# hpctrl.net
KiCad netlist of a schematic drawn in EAGLE
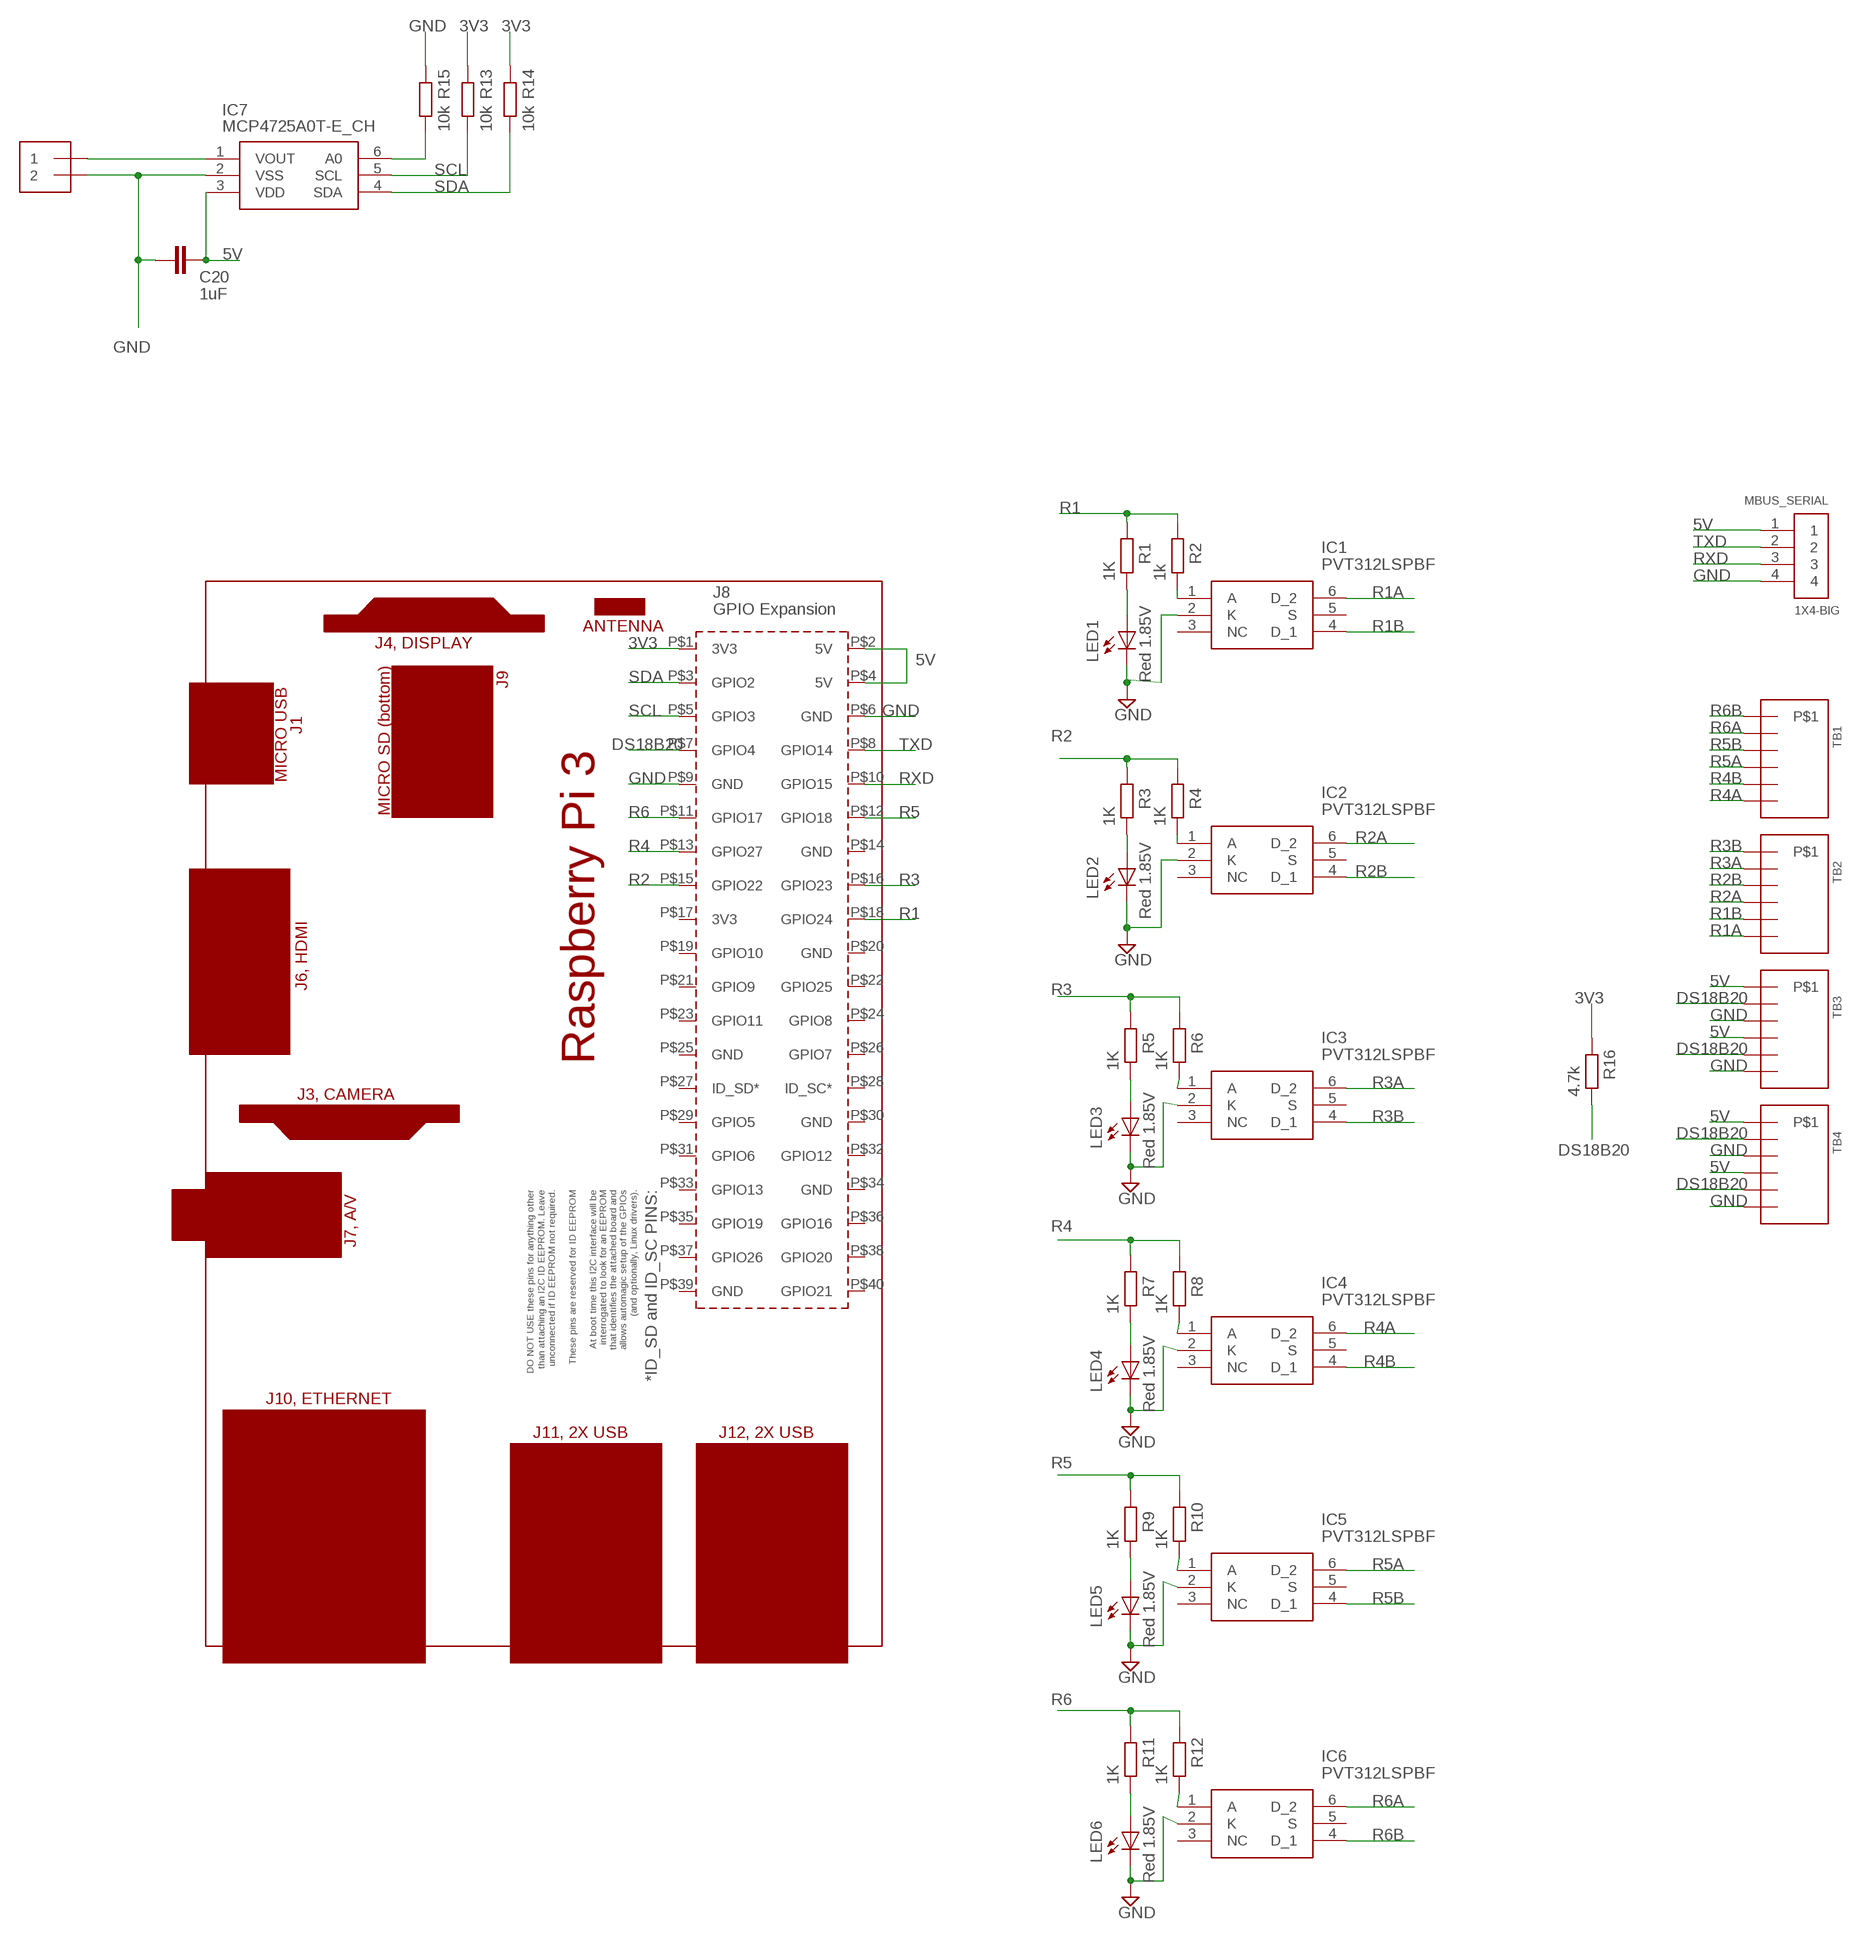
[diagram p0: schematic, sheet 1]

(export (version "E")
  (design (tool "Eeschema 10.0.6"))
  (components
    (comp (ref "C20")
      (value "1uF")
      (footprint "eagle-import:C0805")
      (libsource (lib "eagle-import") (part "C-EUC0805"))
    )
    (comp (ref "IC1")
      (value "PVT312LSPBF")
      (footprint "eagle-import:SOP254P978X342-6N")
      (fields (field (name "MOUSER_PART_NUMBER") "942-PVT312LSPBF"))
      (libsource (lib "eagle-import") (part "PVT312LSPBF"))
    )
    (comp (ref "IC2")
      (value "PVT312LSPBF")
      (footprint "eagle-import:SOP254P978X342-6N")
      (fields (field (name "MOUSER_PART_NUMBER") "942-PVT312LSPBF"))
      (libsource (lib "eagle-import") (part "PVT312LSPBF"))
    )
    (comp (ref "IC3")
      (value "PVT312LSPBF")
      (footprint "eagle-import:SOP254P978X342-6N")
      (fields (field (name "MOUSER_PART_NUMBER") "942-PVT312LSPBF"))
      (libsource (lib "eagle-import") (part "PVT312LSPBF"))
    )
    (comp (ref "IC4")
      (value "PVT312LSPBF")
      (footprint "eagle-import:SOP254P978X342-6N")
      (fields (field (name "MOUSER_PART_NUMBER") "942-PVT312LSPBF"))
      (libsource (lib "eagle-import") (part "PVT312LSPBF"))
    )
    (comp (ref "IC5")
      (value "PVT312LSPBF")
      (footprint "eagle-import:SOP254P978X342-6N")
      (fields (field (name "MOUSER_PART_NUMBER") "942-PVT312LSPBF"))
      (libsource (lib "eagle-import") (part "PVT312LSPBF"))
    )
    (comp (ref "IC6")
      (value "PVT312LSPBF")
      (footprint "eagle-import:SOP254P978X342-6N")
      (fields (field (name "MOUSER_PART_NUMBER") "942-PVT312LSPBF"))
      (libsource (lib "eagle-import") (part "PVT312LSPBF"))
    )
    (comp (ref "IC7")
      (value "MCP4725A0T-E_CH")
      (footprint "eagle-import:SOT95P270X145-6N")
      (fields
        (field (name "ARROW_PART_NUMBER") "MCP4725A0T-E/CH")
        (field (name "MOUSER_PART_NUMBER") "579-MCP4725A0TECH")
      )
      (libsource (lib "eagle-import") (part "MCP4725A0T-E_CH"))
    )
    (comp (ref "J1")
      (value "1X2-3.5MM")
      (footprint "eagle-import:1X2-3.5MM")
      (libsource (lib "eagle-import") (part "1X2-3.5MM"))
    )
    (comp (ref "LED1")
      (value "Red 1.85V")
      (footprint "eagle-import:CHIP-LED0805")
      (libsource (lib "eagle-import") (part "LEDCHIP-LED0805"))
    )
    (comp (ref "LED2")
      (value "Red 1.85V")
      (footprint "eagle-import:CHIP-LED0805")
      (libsource (lib "eagle-import") (part "LEDCHIP-LED0805"))
    )
    (comp (ref "LED3")
      (value "Red 1.85V")
      (footprint "eagle-import:CHIP-LED0805")
      (libsource (lib "eagle-import") (part "LEDCHIP-LED0805"))
    )
    (comp (ref "LED4")
      (value "Red 1.85V")
      (footprint "eagle-import:CHIP-LED0805")
      (libsource (lib "eagle-import") (part "LEDCHIP-LED0805"))
    )
    (comp (ref "LED5")
      (value "Red 1.85V")
      (footprint "eagle-import:CHIP-LED0805")
      (libsource (lib "eagle-import") (part "LEDCHIP-LED0805"))
    )
    (comp (ref "LED6")
      (value "Red 1.85V")
      (footprint "eagle-import:CHIP-LED0805")
      (libsource (lib "eagle-import") (part "LEDCHIP-LED0805"))
    )
    (comp (ref "MBUS_SERIAL")
      (value "1X4-BIG")
      (footprint "eagle-import:1X04-BIG")
      (libsource (lib "eagle-import") (part "1X4-BIG"))
    )
    (comp (ref "PCB1")
      (value "RPI3RPI3")
      (footprint "eagle-import:RPI3")
      (libsource (lib "eagle-import") (part "RPI3RPI3"))
    )
    (comp (ref "R1")
      (value "1K")
      (footprint "eagle-import:R0603")
      (libsource (lib "eagle-import") (part "R-EU_R0603"))
    )
    (comp (ref "R2")
      (value "1k")
      (footprint "eagle-import:R0603")
      (libsource (lib "eagle-import") (part "R-EU_R0603"))
    )
    (comp (ref "R3")
      (value "1K")
      (footprint "eagle-import:R0603")
      (libsource (lib "eagle-import") (part "R-EU_R0603"))
    )
    (comp (ref "R4")
      (value "1K")
      (footprint "eagle-import:R0603")
      (libsource (lib "eagle-import") (part "R-EU_R0603"))
    )
    (comp (ref "R5")
      (value "1K")
      (footprint "eagle-import:R0603")
      (libsource (lib "eagle-import") (part "R-EU_R0603"))
    )
    (comp (ref "R6")
      (value "1K")
      (footprint "eagle-import:R0603")
      (libsource (lib "eagle-import") (part "R-EU_R0603"))
    )
    (comp (ref "R7")
      (value "1K")
      (footprint "eagle-import:R0603")
      (libsource (lib "eagle-import") (part "R-EU_R0603"))
    )
    (comp (ref "R8")
      (value "1K")
      (footprint "eagle-import:R0603")
      (libsource (lib "eagle-import") (part "R-EU_R0603"))
    )
    (comp (ref "R9")
      (value "1K")
      (footprint "eagle-import:R0603")
      (libsource (lib "eagle-import") (part "R-EU_R0603"))
    )
    (comp (ref "R10")
      (value "1K")
      (footprint "eagle-import:R0603")
      (libsource (lib "eagle-import") (part "R-EU_R0603"))
    )
    (comp (ref "R11")
      (value "1K")
      (footprint "eagle-import:R0603")
      (libsource (lib "eagle-import") (part "R-EU_R0603"))
    )
    (comp (ref "R12")
      (value "1K")
      (footprint "eagle-import:R0603")
      (libsource (lib "eagle-import") (part "R-EU_R0603"))
    )
    (comp (ref "R13")
      (value "10k")
      (footprint "eagle-import:R0603")
      (libsource (lib "eagle-import") (part "R-EU_R0603"))
    )
    (comp (ref "R14")
      (value "10k")
      (footprint "eagle-import:R0603")
      (libsource (lib "eagle-import") (part "R-EU_R0603"))
    )
    (comp (ref "R15")
      (value "10k")
      (footprint "eagle-import:R0603")
      (libsource (lib "eagle-import") (part "R-EU_R0603"))
    )
    (comp (ref "R16")
      (value "4.7k")
      (footprint "eagle-import:R0603")
      (libsource (lib "eagle-import") (part "R-EU_R0603"))
    )
    (comp (ref "TB1")
      (value "3.5MM_TB_X6")
      (footprint "eagle-import:3.5MM_X6")
      (libsource (lib "eagle-import") (part "3.5MM_TB_X6"))
    )
    (comp (ref "TB2")
      (value "3.5MM_TB_X6")
      (footprint "eagle-import:3.5MM_X6")
      (libsource (lib "eagle-import") (part "3.5MM_TB_X6"))
    )
    (comp (ref "TB3")
      (value "3.5MM_TB_X6")
      (footprint "eagle-import:3.5MM_X6")
      (libsource (lib "eagle-import") (part "3.5MM_TB_X6"))
    )
    (comp (ref "TB4")
      (value "3.5MM_TB_X6")
      (footprint "eagle-import:3.5MM_X6")
      (libsource (lib "eagle-import") (part "3.5MM_TB_X6"))
    )
  )
  (nets
    (net (code "1") (name "/3V3") (class "Default")
      (node (ref "PCB1") (pin "P$1") (pinfunction "3V3_P$1") (pintype "bidirectional"))
      (node (ref "R13") (pin "2") (pinfunction "2_2") (pintype "passive"))
      (node (ref "R14") (pin "2") (pinfunction "2_2") (pintype "passive"))
      (node (ref "R16") (pin "2") (pinfunction "2_2") (pintype "passive"))
    )
    (net (code "2") (name "/5V") (class "Default")
      (node (ref "C20") (pin "1") (pinfunction "1_1") (pintype "passive"))
      (node (ref "IC7") (pin "3") (pinfunction "VDD_3") (pintype "bidirectional"))
      (node (ref "MBUS_SERIAL") (pin "1") (pinfunction "1_1") (pintype "bidirectional"))
      (node (ref "PCB1") (pin "P$2") (pinfunction "5V_P$2") (pintype "bidirectional"))
      (node (ref "PCB1") (pin "P$4") (pinfunction "5V_P$4") (pintype "bidirectional"))
      (node (ref "TB3") (pin "P$1") (pinfunction "P$1_P$1") (pintype "bidirectional"))
      (node (ref "TB3") (pin "P$4") (pinfunction "P$4_P$4") (pintype "bidirectional"))
      (node (ref "TB4") (pin "P$1") (pinfunction "P$1_P$1") (pintype "bidirectional"))
      (node (ref "TB4") (pin "P$4") (pinfunction "P$4_P$4") (pintype "bidirectional"))
    )
    (net (code "3") (name "/DS18B20") (class "Default")
      (node (ref "PCB1") (pin "P$7") (pinfunction "GPIO4_P$7") (pintype "bidirectional"))
      (node (ref "R16") (pin "1") (pinfunction "1_1") (pintype "passive"))
      (node (ref "TB3") (pin "P$2") (pinfunction "P$2_P$2") (pintype "bidirectional"))
      (node (ref "TB3") (pin "P$5") (pinfunction "P$5_P$5") (pintype "bidirectional"))
      (node (ref "TB4") (pin "P$2") (pinfunction "P$2_P$2") (pintype "bidirectional"))
      (node (ref "TB4") (pin "P$5") (pinfunction "P$5_P$5") (pintype "bidirectional"))
    )
    (net (code "4") (name "/R1") (class "Default")
      (node (ref "PCB1") (pin "P$18") (pinfunction "GPIO24_P$18") (pintype "bidirectional"))
      (node (ref "R1") (pin "2") (pinfunction "2_2") (pintype "passive"))
      (node (ref "R2") (pin "2") (pinfunction "2_2") (pintype "passive"))
    )
    (net (code "5") (name "/R1A") (class "Default")
      (node (ref "IC1") (pin "6") (pinfunction "D_2_6") (pintype "bidirectional"))
      (node (ref "TB2") (pin "P$6") (pinfunction "P$6_P$6") (pintype "bidirectional"))
    )
    (net (code "6") (name "/R1B") (class "Default")
      (node (ref "IC1") (pin "4") (pinfunction "D_1_4") (pintype "bidirectional"))
      (node (ref "TB2") (pin "P$5") (pinfunction "P$5_P$5") (pintype "bidirectional"))
    )
    (net (code "7") (name "/R2") (class "Default")
      (node (ref "PCB1") (pin "P$15") (pinfunction "GPIO22_P$15") (pintype "bidirectional"))
      (node (ref "R3") (pin "2") (pinfunction "2_2") (pintype "passive"))
      (node (ref "R4") (pin "2") (pinfunction "2_2") (pintype "passive"))
    )
    (net (code "8") (name "/R2A") (class "Default")
      (node (ref "IC2") (pin "6") (pinfunction "D_2_6") (pintype "bidirectional"))
      (node (ref "TB2") (pin "P$4") (pinfunction "P$4_P$4") (pintype "bidirectional"))
    )
    (net (code "9") (name "/R2B") (class "Default")
      (node (ref "IC2") (pin "4") (pinfunction "D_1_4") (pintype "bidirectional"))
      (node (ref "TB2") (pin "P$3") (pinfunction "P$3_P$3") (pintype "bidirectional"))
    )
    (net (code "10") (name "/R3") (class "Default")
      (node (ref "PCB1") (pin "P$16") (pinfunction "GPIO23_P$16") (pintype "bidirectional"))
      (node (ref "R5") (pin "2") (pinfunction "2_2") (pintype "passive"))
      (node (ref "R6") (pin "2") (pinfunction "2_2") (pintype "passive"))
    )
    (net (code "11") (name "/R3A") (class "Default")
      (node (ref "IC3") (pin "6") (pinfunction "D_2_6") (pintype "bidirectional"))
      (node (ref "TB2") (pin "P$2") (pinfunction "P$2_P$2") (pintype "bidirectional"))
    )
    (net (code "12") (name "/R3B") (class "Default")
      (node (ref "IC3") (pin "4") (pinfunction "D_1_4") (pintype "bidirectional"))
      (node (ref "TB2") (pin "P$1") (pinfunction "P$1_P$1") (pintype "bidirectional"))
    )
    (net (code "13") (name "/R4") (class "Default")
      (node (ref "PCB1") (pin "P$13") (pinfunction "GPIO27_P$13") (pintype "bidirectional"))
      (node (ref "R7") (pin "2") (pinfunction "2_2") (pintype "passive"))
      (node (ref "R8") (pin "2") (pinfunction "2_2") (pintype "passive"))
    )
    (net (code "14") (name "/R4A") (class "Default")
      (node (ref "IC4") (pin "6") (pinfunction "D_2_6") (pintype "bidirectional"))
      (node (ref "TB1") (pin "P$6") (pinfunction "P$6_P$6") (pintype "bidirectional"))
    )
    (net (code "15") (name "/R4B") (class "Default")
      (node (ref "IC4") (pin "4") (pinfunction "D_1_4") (pintype "bidirectional"))
      (node (ref "TB1") (pin "P$5") (pinfunction "P$5_P$5") (pintype "bidirectional"))
    )
    (net (code "16") (name "/R5") (class "Default")
      (node (ref "PCB1") (pin "P$12") (pinfunction "GPIO18_P$12") (pintype "bidirectional"))
      (node (ref "R10") (pin "2") (pinfunction "2_2") (pintype "passive"))
      (node (ref "R9") (pin "2") (pinfunction "2_2") (pintype "passive"))
    )
    (net (code "17") (name "/R5A") (class "Default")
      (node (ref "IC5") (pin "6") (pinfunction "D_2_6") (pintype "bidirectional"))
      (node (ref "TB1") (pin "P$4") (pinfunction "P$4_P$4") (pintype "bidirectional"))
    )
    (net (code "18") (name "/R5B") (class "Default")
      (node (ref "IC5") (pin "4") (pinfunction "D_1_4") (pintype "bidirectional"))
      (node (ref "TB1") (pin "P$3") (pinfunction "P$3_P$3") (pintype "bidirectional"))
    )
    (net (code "19") (name "/R6") (class "Default")
      (node (ref "PCB1") (pin "P$11") (pinfunction "GPIO17_P$11") (pintype "bidirectional"))
      (node (ref "R11") (pin "2") (pinfunction "2_2") (pintype "passive"))
      (node (ref "R12") (pin "2") (pinfunction "2_2") (pintype "passive"))
    )
    (net (code "20") (name "/R6A") (class "Default")
      (node (ref "IC6") (pin "6") (pinfunction "D_2_6") (pintype "bidirectional"))
      (node (ref "TB1") (pin "P$2") (pinfunction "P$2_P$2") (pintype "bidirectional"))
    )
    (net (code "21") (name "/R6B") (class "Default")
      (node (ref "IC6") (pin "4") (pinfunction "D_1_4") (pintype "bidirectional"))
      (node (ref "TB1") (pin "P$1") (pinfunction "P$1_P$1") (pintype "bidirectional"))
    )
    (net (code "22") (name "/RXD") (class "Default")
      (node (ref "MBUS_SERIAL") (pin "3") (pinfunction "3_3") (pintype "bidirectional"))
      (node (ref "PCB1") (pin "P$10") (pinfunction "GPIO15_P$10") (pintype "bidirectional"))
    )
    (net (code "23") (name "/SCL") (class "Default")
      (node (ref "IC7") (pin "5") (pinfunction "SCL_5") (pintype "bidirectional"))
      (node (ref "PCB1") (pin "P$5") (pinfunction "GPIO3_P$5") (pintype "bidirectional"))
      (node (ref "R13") (pin "1") (pinfunction "1_1") (pintype "passive"))
    )
    (net (code "24") (name "/SDA") (class "Default")
      (node (ref "IC7") (pin "4") (pinfunction "SDA_4") (pintype "bidirectional"))
      (node (ref "PCB1") (pin "P$3") (pinfunction "GPIO2_P$3") (pintype "bidirectional"))
      (node (ref "R14") (pin "1") (pinfunction "1_1") (pintype "passive"))
    )
    (net (code "25") (name "/TXD") (class "Default")
      (node (ref "MBUS_SERIAL") (pin "2") (pinfunction "2_2") (pintype "bidirectional"))
      (node (ref "PCB1") (pin "P$8") (pinfunction "GPIO14_P$8") (pintype "bidirectional"))
    )
    (net (code "26") (name "GND") (class "Default")
      (node (ref "C20") (pin "2") (pinfunction "2_2") (pintype "passive"))
      (node (ref "IC1") (pin "2") (pinfunction "K_2") (pintype "bidirectional"))
      (node (ref "IC2") (pin "2") (pinfunction "K_2") (pintype "bidirectional"))
      (node (ref "IC3") (pin "2") (pinfunction "K_2") (pintype "bidirectional"))
      (node (ref "IC4") (pin "2") (pinfunction "K_2") (pintype "bidirectional"))
      (node (ref "IC5") (pin "2") (pinfunction "K_2") (pintype "bidirectional"))
      (node (ref "IC6") (pin "2") (pinfunction "K_2") (pintype "bidirectional"))
      (node (ref "IC7") (pin "2") (pinfunction "VSS_2") (pintype "bidirectional"))
      (node (ref "J1") (pin "2") (pinfunction "2_2") (pintype "passive"))
      (node (ref "LED1") (pin "C") (pinfunction "C_C") (pintype "passive"))
      (node (ref "LED2") (pin "C") (pinfunction "C_C") (pintype "passive"))
      (node (ref "LED3") (pin "C") (pinfunction "C_C") (pintype "passive"))
      (node (ref "LED4") (pin "C") (pinfunction "C_C") (pintype "passive"))
      (node (ref "LED5") (pin "C") (pinfunction "C_C") (pintype "passive"))
      (node (ref "LED6") (pin "C") (pinfunction "C_C") (pintype "passive"))
      (node (ref "MBUS_SERIAL") (pin "4") (pinfunction "4_4") (pintype "bidirectional"))
      (node (ref "PCB1") (pin "P$6") (pinfunction "GND_P$6") (pintype "bidirectional"))
      (node (ref "PCB1") (pin "P$9") (pinfunction "GND_P$9") (pintype "bidirectional"))
      (node (ref "R15") (pin "2") (pinfunction "2_2") (pintype "passive"))
      (node (ref "TB3") (pin "P$3") (pinfunction "P$3_P$3") (pintype "bidirectional"))
      (node (ref "TB3") (pin "P$6") (pinfunction "P$6_P$6") (pintype "bidirectional"))
      (node (ref "TB4") (pin "P$3") (pinfunction "P$3_P$3") (pintype "bidirectional"))
      (node (ref "TB4") (pin "P$6") (pinfunction "P$6_P$6") (pintype "bidirectional"))
    )
    (net (code "27") (name "Net-(IC1-A)") (class "Default")
      (node (ref "IC1") (pin "1") (pinfunction "A_1") (pintype "bidirectional"))
      (node (ref "R2") (pin "1") (pinfunction "1_1") (pintype "passive"))
    )
    (net (code "28") (name "Net-(IC2-A)") (class "Default")
      (node (ref "IC2") (pin "1") (pinfunction "A_1") (pintype "bidirectional"))
      (node (ref "R4") (pin "1") (pinfunction "1_1") (pintype "passive"))
    )
    (net (code "29") (name "Net-(IC3-A)") (class "Default")
      (node (ref "IC3") (pin "1") (pinfunction "A_1") (pintype "bidirectional"))
      (node (ref "R6") (pin "1") (pinfunction "1_1") (pintype "passive"))
    )
    (net (code "30") (name "Net-(IC4-A)") (class "Default")
      (node (ref "IC4") (pin "1") (pinfunction "A_1") (pintype "bidirectional"))
      (node (ref "R8") (pin "1") (pinfunction "1_1") (pintype "passive"))
    )
    (net (code "31") (name "Net-(IC5-A)") (class "Default")
      (node (ref "IC5") (pin "1") (pinfunction "A_1") (pintype "bidirectional"))
      (node (ref "R10") (pin "1") (pinfunction "1_1") (pintype "passive"))
    )
    (net (code "32") (name "Net-(IC6-A)") (class "Default")
      (node (ref "IC6") (pin "1") (pinfunction "A_1") (pintype "bidirectional"))
      (node (ref "R12") (pin "1") (pinfunction "1_1") (pintype "passive"))
    )
    (net (code "33") (name "Net-(IC7-A0)") (class "Default")
      (node (ref "IC7") (pin "6") (pinfunction "A0_6") (pintype "bidirectional"))
      (node (ref "R15") (pin "1") (pinfunction "1_1") (pintype "passive"))
    )
    (net (code "34") (name "Net-(IC7-VOUT)") (class "Default")
      (node (ref "IC7") (pin "1") (pinfunction "VOUT_1") (pintype "bidirectional"))
      (node (ref "J1") (pin "1") (pinfunction "1_1") (pintype "passive"))
    )
    (net (code "35") (name "Net-(LED1-PadA)") (class "Default")
      (node (ref "LED1") (pin "A") (pinfunction "A_A") (pintype "passive"))
      (node (ref "R1") (pin "1") (pinfunction "1_1") (pintype "passive"))
    )
    (net (code "36") (name "Net-(LED2-PadA)") (class "Default")
      (node (ref "LED2") (pin "A") (pinfunction "A_A") (pintype "passive"))
      (node (ref "R3") (pin "1") (pinfunction "1_1") (pintype "passive"))
    )
    (net (code "37") (name "Net-(LED3-PadA)") (class "Default")
      (node (ref "LED3") (pin "A") (pinfunction "A_A") (pintype "passive"))
      (node (ref "R5") (pin "1") (pinfunction "1_1") (pintype "passive"))
    )
    (net (code "38") (name "Net-(LED4-PadA)") (class "Default")
      (node (ref "LED4") (pin "A") (pinfunction "A_A") (pintype "passive"))
      (node (ref "R7") (pin "1") (pinfunction "1_1") (pintype "passive"))
    )
    (net (code "39") (name "Net-(LED5-PadA)") (class "Default")
      (node (ref "LED5") (pin "A") (pinfunction "A_A") (pintype "passive"))
      (node (ref "R9") (pin "1") (pinfunction "1_1") (pintype "passive"))
    )
    (net (code "40") (name "Net-(LED6-PadA)") (class "Default")
      (node (ref "LED6") (pin "A") (pinfunction "A_A") (pintype "passive"))
      (node (ref "R11") (pin "1") (pinfunction "1_1") (pintype "passive"))
    )
    (net (code "41") (name "unconnected-(IC1-NC-Pad3)") (class "Default")
      (node (ref "IC1") (pin "3") (pinfunction "NC_3") (pintype "no_connect"))
    )
    (net (code "42") (name "unconnected-(IC1-S-Pad5)") (class "Default")
      (node (ref "IC1") (pin "5") (pinfunction "S_5") (pintype "bidirectional"))
    )
    (net (code "43") (name "unconnected-(IC2-NC-Pad3)") (class "Default")
      (node (ref "IC2") (pin "3") (pinfunction "NC_3") (pintype "no_connect"))
    )
    (net (code "44") (name "unconnected-(IC2-S-Pad5)") (class "Default")
      (node (ref "IC2") (pin "5") (pinfunction "S_5") (pintype "bidirectional"))
    )
    (net (code "45") (name "unconnected-(IC3-NC-Pad3)") (class "Default")
      (node (ref "IC3") (pin "3") (pinfunction "NC_3") (pintype "no_connect"))
    )
    (net (code "46") (name "unconnected-(IC3-S-Pad5)") (class "Default")
      (node (ref "IC3") (pin "5") (pinfunction "S_5") (pintype "bidirectional"))
    )
    (net (code "47") (name "unconnected-(IC4-NC-Pad3)") (class "Default")
      (node (ref "IC4") (pin "3") (pinfunction "NC_3") (pintype "no_connect"))
    )
    (net (code "48") (name "unconnected-(IC4-S-Pad5)") (class "Default")
      (node (ref "IC4") (pin "5") (pinfunction "S_5") (pintype "bidirectional"))
    )
    (net (code "49") (name "unconnected-(IC5-NC-Pad3)") (class "Default")
      (node (ref "IC5") (pin "3") (pinfunction "NC_3") (pintype "no_connect"))
    )
    (net (code "50") (name "unconnected-(IC5-S-Pad5)") (class "Default")
      (node (ref "IC5") (pin "5") (pinfunction "S_5") (pintype "bidirectional"))
    )
    (net (code "51") (name "unconnected-(IC6-NC-Pad3)") (class "Default")
      (node (ref "IC6") (pin "3") (pinfunction "NC_3") (pintype "no_connect"))
    )
    (net (code "52") (name "unconnected-(IC6-S-Pad5)") (class "Default")
      (node (ref "IC6") (pin "5") (pinfunction "S_5") (pintype "bidirectional"))
    )
    (net (code "53") (name "unconnected-(PCB1-3V3-PadP$17)") (class "Default")
      (node (ref "PCB1") (pin "P$17") (pinfunction "3V3_P$17") (pintype "bidirectional"))
    )
    (net (code "54") (name "unconnected-(PCB1-GND-PadP$14)") (class "Default")
      (node (ref "PCB1") (pin "P$14") (pinfunction "GND_P$14") (pintype "bidirectional"))
    )
    (net (code "55") (name "unconnected-(PCB1-GND-PadP$20)") (class "Default")
      (node (ref "PCB1") (pin "P$20") (pinfunction "GND_P$20") (pintype "bidirectional"))
    )
    (net (code "56") (name "unconnected-(PCB1-GND-PadP$25)") (class "Default")
      (node (ref "PCB1") (pin "P$25") (pinfunction "GND_P$25") (pintype "bidirectional"))
    )
    (net (code "57") (name "unconnected-(PCB1-GND-PadP$30)") (class "Default")
      (node (ref "PCB1") (pin "P$30") (pinfunction "GND_P$30") (pintype "bidirectional"))
    )
    (net (code "58") (name "unconnected-(PCB1-GND-PadP$34)") (class "Default")
      (node (ref "PCB1") (pin "P$34") (pinfunction "GND_P$34") (pintype "bidirectional"))
    )
    (net (code "59") (name "unconnected-(PCB1-GND-PadP$39)") (class "Default")
      (node (ref "PCB1") (pin "P$39") (pinfunction "GND_P$39") (pintype "bidirectional"))
    )
    (net (code "60") (name "unconnected-(PCB1-GPIO5-PadP$29)") (class "Default")
      (node (ref "PCB1") (pin "P$29") (pinfunction "GPIO5_P$29") (pintype "bidirectional"))
    )
    (net (code "61") (name "unconnected-(PCB1-GPIO6-PadP$31)") (class "Default")
      (node (ref "PCB1") (pin "P$31") (pinfunction "GPIO6_P$31") (pintype "bidirectional"))
    )
    (net (code "62") (name "unconnected-(PCB1-GPIO7-PadP$26)") (class "Default")
      (node (ref "PCB1") (pin "P$26") (pinfunction "GPIO7_P$26") (pintype "bidirectional"))
    )
    (net (code "63") (name "unconnected-(PCB1-GPIO8-PadP$24)") (class "Default")
      (node (ref "PCB1") (pin "P$24") (pinfunction "GPIO8_P$24") (pintype "bidirectional"))
    )
    (net (code "64") (name "unconnected-(PCB1-GPIO9-PadP$21)") (class "Default")
      (node (ref "PCB1") (pin "P$21") (pinfunction "GPIO9_P$21") (pintype "bidirectional"))
    )
    (net (code "65") (name "unconnected-(PCB1-GPIO10-PadP$19)") (class "Default")
      (node (ref "PCB1") (pin "P$19") (pinfunction "GPIO10_P$19") (pintype "bidirectional"))
    )
    (net (code "66") (name "unconnected-(PCB1-GPIO11-PadP$23)") (class "Default")
      (node (ref "PCB1") (pin "P$23") (pinfunction "GPIO11_P$23") (pintype "bidirectional"))
    )
    (net (code "67") (name "unconnected-(PCB1-GPIO12-PadP$32)") (class "Default")
      (node (ref "PCB1") (pin "P$32") (pinfunction "GPIO12_P$32") (pintype "bidirectional"))
    )
    (net (code "68") (name "unconnected-(PCB1-GPIO13-PadP$33)") (class "Default")
      (node (ref "PCB1") (pin "P$33") (pinfunction "GPIO13_P$33") (pintype "bidirectional"))
    )
    (net (code "69") (name "unconnected-(PCB1-GPIO16-PadP$36)") (class "Default")
      (node (ref "PCB1") (pin "P$36") (pinfunction "GPIO16_P$36") (pintype "bidirectional"))
    )
    (net (code "70") (name "unconnected-(PCB1-GPIO19-PadP$35)") (class "Default")
      (node (ref "PCB1") (pin "P$35") (pinfunction "GPIO19_P$35") (pintype "bidirectional"))
    )
    (net (code "71") (name "unconnected-(PCB1-GPIO20-PadP$38)") (class "Default")
      (node (ref "PCB1") (pin "P$38") (pinfunction "GPIO20_P$38") (pintype "bidirectional"))
    )
    (net (code "72") (name "unconnected-(PCB1-GPIO21-PadP$40)") (class "Default")
      (node (ref "PCB1") (pin "P$40") (pinfunction "GPIO21_P$40") (pintype "bidirectional"))
    )
    (net (code "73") (name "unconnected-(PCB1-GPIO25-PadP$22)") (class "Default")
      (node (ref "PCB1") (pin "P$22") (pinfunction "GPIO25_P$22") (pintype "bidirectional"))
    )
    (net (code "74") (name "unconnected-(PCB1-GPIO26-PadP$37)") (class "Default")
      (node (ref "PCB1") (pin "P$37") (pinfunction "GPIO26_P$37") (pintype "bidirectional"))
    )
    (net (code "75") (name "unconnected-(PCB1-ID_SC*-PadP$28)") (class "Default")
      (node (ref "PCB1") (pin "P$28") (pinfunction "ID_SC*_P$28") (pintype "bidirectional"))
    )
    (net (code "76") (name "unconnected-(PCB1-ID_SD*-PadP$27)") (class "Default")
      (node (ref "PCB1") (pin "P$27") (pinfunction "ID_SD*_P$27") (pintype "bidirectional"))
    )
  )
)
